# Top.net
KiCad netlist of a schematic drawn in Altium Designer
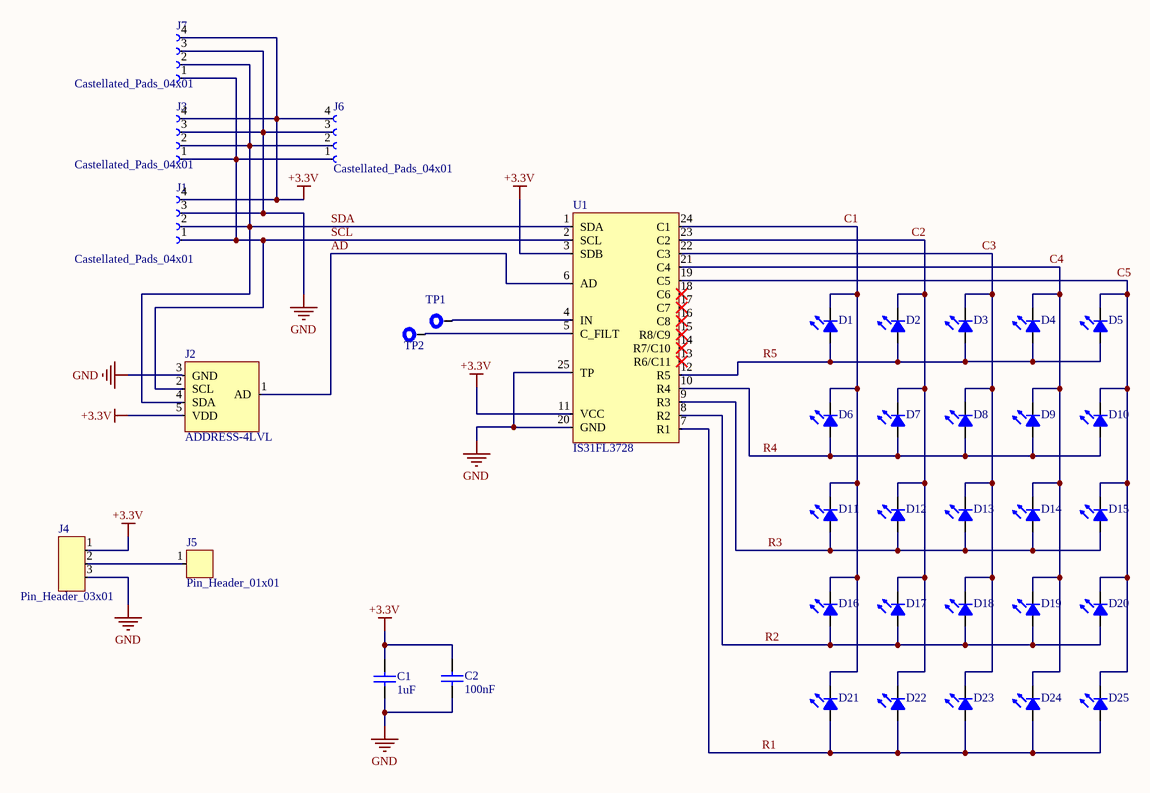
[diagram p0: Top.SchDoc]

(export (version "E")
  (design (tool "Eeschema 10.0.6"))
  (components
    (comp (ref "C1")
      (value "1uF")
      (footprint "CAP_0603")
      (fields (field (name "Comment") "CAP"))
      (libsource (lib "Passive") (part "CAP"))
    )
    (comp (ref "C2")
      (value "100nF")
      (footprint "CAP_0603")
      (fields (field (name "Comment") "CAP"))
      (libsource (lib "Passive") (part "CAP"))
    )
    (comp (ref "D1")
      (value "LED")
      (footprint "LED_0805")
      (fields (field (name "MANUFACTURER") "ROHM Semiconductor"))
      (libsource (lib "Rohm_Semi") (part "LED"))
    )
    (comp (ref "D2")
      (value "LED")
      (footprint "LED_0805")
      (fields (field (name "MANUFACTURER") "ROHM Semiconductor"))
      (libsource (lib "Rohm_Semi") (part "LED"))
    )
    (comp (ref "D3")
      (value "LED")
      (footprint "LED_0805")
      (fields (field (name "MANUFACTURER") "ROHM Semiconductor"))
      (libsource (lib "Rohm_Semi") (part "LED"))
    )
    (comp (ref "D4")
      (value "LED")
      (footprint "LED_0805")
      (fields (field (name "MANUFACTURER") "ROHM Semiconductor"))
      (libsource (lib "Rohm_Semi") (part "LED"))
    )
    (comp (ref "D5")
      (value "LED")
      (footprint "LED_0805")
      (fields (field (name "MANUFACTURER") "ROHM Semiconductor"))
      (libsource (lib "Rohm_Semi") (part "LED"))
    )
    (comp (ref "D6")
      (value "LED")
      (footprint "LED_0805")
      (fields (field (name "MANUFACTURER") "ROHM Semiconductor"))
      (libsource (lib "Rohm_Semi") (part "LED"))
    )
    (comp (ref "D7")
      (value "LED")
      (footprint "LED_0805")
      (fields (field (name "MANUFACTURER") "ROHM Semiconductor"))
      (libsource (lib "Rohm_Semi") (part "LED"))
    )
    (comp (ref "D8")
      (value "LED")
      (footprint "LED_0805")
      (fields (field (name "MANUFACTURER") "ROHM Semiconductor"))
      (libsource (lib "Rohm_Semi") (part "LED"))
    )
    (comp (ref "D9")
      (value "LED")
      (footprint "LED_0805")
      (fields (field (name "MANUFACTURER") "ROHM Semiconductor"))
      (libsource (lib "Rohm_Semi") (part "LED"))
    )
    (comp (ref "D10")
      (value "LED")
      (footprint "LED_0805")
      (fields (field (name "MANUFACTURER") "ROHM Semiconductor"))
      (libsource (lib "Rohm_Semi") (part "LED"))
    )
    (comp (ref "D11")
      (value "LED")
      (footprint "LED_0805")
      (fields (field (name "MANUFACTURER") "ROHM Semiconductor"))
      (libsource (lib "Rohm_Semi") (part "LED"))
    )
    (comp (ref "D12")
      (value "LED")
      (footprint "LED_0805")
      (fields (field (name "MANUFACTURER") "ROHM Semiconductor"))
      (libsource (lib "Rohm_Semi") (part "LED"))
    )
    (comp (ref "D13")
      (value "LED")
      (footprint "LED_0805")
      (fields (field (name "MANUFACTURER") "ROHM Semiconductor"))
      (libsource (lib "Rohm_Semi") (part "LED"))
    )
    (comp (ref "D14")
      (value "LED")
      (footprint "LED_0805")
      (fields (field (name "MANUFACTURER") "ROHM Semiconductor"))
      (libsource (lib "Rohm_Semi") (part "LED"))
    )
    (comp (ref "D15")
      (value "LED")
      (footprint "LED_0805")
      (fields (field (name "MANUFACTURER") "ROHM Semiconductor"))
      (libsource (lib "Rohm_Semi") (part "LED"))
    )
    (comp (ref "D16")
      (value "LED")
      (footprint "LED_0805")
      (fields (field (name "MANUFACTURER") "ROHM Semiconductor"))
      (libsource (lib "Rohm_Semi") (part "LED"))
    )
    (comp (ref "D17")
      (value "LED")
      (footprint "LED_0805")
      (fields (field (name "MANUFACTURER") "ROHM Semiconductor"))
      (libsource (lib "Rohm_Semi") (part "LED"))
    )
    (comp (ref "D18")
      (value "LED")
      (footprint "LED_0805")
      (fields (field (name "MANUFACTURER") "ROHM Semiconductor"))
      (libsource (lib "Rohm_Semi") (part "LED"))
    )
    (comp (ref "D19")
      (value "LED")
      (footprint "LED_0805")
      (fields (field (name "MANUFACTURER") "ROHM Semiconductor"))
      (libsource (lib "Rohm_Semi") (part "LED"))
    )
    (comp (ref "D20")
      (value "LED")
      (footprint "LED_0805")
      (fields (field (name "MANUFACTURER") "ROHM Semiconductor"))
      (libsource (lib "Rohm_Semi") (part "LED"))
    )
    (comp (ref "D21")
      (value "LED")
      (footprint "LED_0805")
      (fields (field (name "MANUFACTURER") "ROHM Semiconductor"))
      (libsource (lib "Rohm_Semi") (part "LED"))
    )
    (comp (ref "D22")
      (value "LED")
      (footprint "LED_0805")
      (fields (field (name "MANUFACTURER") "ROHM Semiconductor"))
      (libsource (lib "Rohm_Semi") (part "LED"))
    )
    (comp (ref "D23")
      (value "LED")
      (footprint "LED_0805")
      (fields (field (name "MANUFACTURER") "ROHM Semiconductor"))
      (libsource (lib "Rohm_Semi") (part "LED"))
    )
    (comp (ref "D24")
      (value "LED")
      (footprint "LED_0805")
      (fields (field (name "MANUFACTURER") "ROHM Semiconductor"))
      (libsource (lib "Rohm_Semi") (part "LED"))
    )
    (comp (ref "D25")
      (value "LED")
      (footprint "LED_0805")
      (fields (field (name "MANUFACTURER") "ROHM Semiconductor"))
      (libsource (lib "Rohm_Semi") (part "LED"))
    )
    (comp (ref "J1")
      (value "Castellated_Pads_04x01")
      (footprint "04X01_Castellated_Pad_1MM")
      (libsource (lib "Connectors") (part "Castellated_Pads_04x01"))
    )
    (comp (ref "J2")
      (value "ADDRESS-4LVL")
      (footprint "ADDRESS-4LVL")
      (libsource (lib "SolderJumper") (part "ADDRESS-4LVL"))
    )
    (comp (ref "J3")
      (value "Castellated_Pads_04x01")
      (footprint "04X01_Castellated_Pad_1MM")
      (libsource (lib "Connectors") (part "Castellated_Pads_04x01"))
    )
    (comp (ref "J4")
      (value "Pin_Header_03x01")
      (footprint "03x01_Header_5mm_MAL_DOWN")
      (libsource (lib "Connectors") (part "Pin_Header_03x01"))
    )
    (comp (ref "J5")
      (value "Pin_Header_01x01")
      (footprint "01x01_Header_2.54mm_MAL")
      (libsource (lib "Connectors") (part "Pin_Header_01x01"))
    )
    (comp (ref "J6")
      (value "Castellated_Pads_04x01")
      (footprint "04X01_Castellated_Pad_1MM")
      (libsource (lib "") (part "Castellated_Pads_04x01_1"))
    )
    (comp (ref "J7")
      (value "Castellated_Pads_04x01")
      (footprint "04X01_Castellated_Pad_1MM")
      (libsource (lib "Connectors") (part "Castellated_Pads_04x01"))
    )
    (comp (ref "TP1")
      (value "Testpoint 2mm")
      (footprint "TESTPOINT")
      (libsource (lib "Testpoint") (part "Testpoint 2mm"))
    )
    (comp (ref "TP2")
      (value "Testpoint 2mm")
      (footprint "TESTPOINT")
      (libsource (lib "Testpoint") (part "Testpoint 2mm"))
    )
    (comp (ref "U1")
      (value "IS31FL3728")
      (footprint "QFN50P395X400X80_HS-25N")
      (description "8x8 IIC Led Driver")
      (fields (field (name "MANUFACTURER") "ISSI"))
      (libsource (lib "ISSI") (part "IS31FL3728"))
    )
  )
  (nets
    (net (code "1") (name "+3.3V") (class "Default")
      (node (ref "C1") (pin "2") (pinfunction "2_2") (pintype "passive"))
      (node (ref "C2") (pin "2") (pinfunction "2_2") (pintype "passive"))
      (node (ref "J1") (pin "4") (pintype "passive"))
      (node (ref "J2") (pin "5") (pinfunction "VDD_5") (pintype "passive"))
      (node (ref "J3") (pin "4") (pintype "passive"))
      (node (ref "J4") (pin "1") (pintype "passive"))
      (node (ref "J6") (pin "4") (pintype "passive"))
      (node (ref "J7") (pin "4") (pintype "passive"))
      (node (ref "U1") (pin "11") (pinfunction "VCC_11") (pintype "power_in"))
      (node (ref "U1") (pin "3") (pinfunction "SDB_3") (pintype "input"))
    )
    (net (code "2") (name "/AD") (class "Default")
      (node (ref "J2") (pin "1") (pinfunction "AD_1") (pintype "passive"))
      (node (ref "U1") (pin "6") (pinfunction "AD_6") (pintype "input"))
    )
    (net (code "3") (name "/C1") (class "Default")
      (node (ref "D1") (pin "1") (pinfunction "K_1") (pintype "passive"))
      (node (ref "D11") (pin "1") (pinfunction "K_1") (pintype "passive"))
      (node (ref "D16") (pin "1") (pinfunction "K_1") (pintype "passive"))
      (node (ref "D21") (pin "1") (pinfunction "K_1") (pintype "passive"))
      (node (ref "D6") (pin "1") (pinfunction "K_1") (pintype "passive"))
      (node (ref "U1") (pin "24") (pinfunction "C1_24") (pintype "bidirectional"))
    )
    (net (code "4") (name "/C2") (class "Default")
      (node (ref "D12") (pin "1") (pinfunction "K_1") (pintype "passive"))
      (node (ref "D17") (pin "1") (pinfunction "K_1") (pintype "passive"))
      (node (ref "D2") (pin "1") (pinfunction "K_1") (pintype "passive"))
      (node (ref "D22") (pin "1") (pinfunction "K_1") (pintype "passive"))
      (node (ref "D7") (pin "1") (pinfunction "K_1") (pintype "passive"))
      (node (ref "U1") (pin "23") (pinfunction "C2_23") (pintype "bidirectional"))
    )
    (net (code "5") (name "/C3") (class "Default")
      (node (ref "D13") (pin "1") (pinfunction "K_1") (pintype "passive"))
      (node (ref "D18") (pin "1") (pinfunction "K_1") (pintype "passive"))
      (node (ref "D23") (pin "1") (pinfunction "K_1") (pintype "passive"))
      (node (ref "D3") (pin "1") (pinfunction "K_1") (pintype "passive"))
      (node (ref "D8") (pin "1") (pinfunction "K_1") (pintype "passive"))
      (node (ref "U1") (pin "22") (pinfunction "C3_22") (pintype "bidirectional"))
    )
    (net (code "6") (name "/C4") (class "Default")
      (node (ref "D14") (pin "1") (pinfunction "K_1") (pintype "passive"))
      (node (ref "D19") (pin "1") (pinfunction "K_1") (pintype "passive"))
      (node (ref "D24") (pin "1") (pinfunction "K_1") (pintype "passive"))
      (node (ref "D4") (pin "1") (pinfunction "K_1") (pintype "passive"))
      (node (ref "D9") (pin "1") (pinfunction "K_1") (pintype "passive"))
      (node (ref "U1") (pin "21") (pinfunction "C4_21") (pintype "bidirectional"))
    )
    (net (code "7") (name "/C5") (class "Default")
      (node (ref "D10") (pin "1") (pinfunction "K_1") (pintype "passive"))
      (node (ref "D15") (pin "1") (pinfunction "K_1") (pintype "passive"))
      (node (ref "D20") (pin "1") (pinfunction "K_1") (pintype "passive"))
      (node (ref "D25") (pin "1") (pinfunction "K_1") (pintype "passive"))
      (node (ref "D5") (pin "1") (pinfunction "K_1") (pintype "passive"))
      (node (ref "U1") (pin "19") (pinfunction "C5_19") (pintype "bidirectional"))
    )
    (net (code "8") (name "/R1") (class "Default")
      (node (ref "D21") (pin "2") (pinfunction "A_2") (pintype "passive"))
      (node (ref "D22") (pin "2") (pinfunction "A_2") (pintype "passive"))
      (node (ref "D23") (pin "2") (pinfunction "A_2") (pintype "passive"))
      (node (ref "D24") (pin "2") (pinfunction "A_2") (pintype "passive"))
      (node (ref "D25") (pin "2") (pinfunction "A_2") (pintype "passive"))
      (node (ref "U1") (pin "7") (pinfunction "R1_7") (pintype "bidirectional"))
    )
    (net (code "9") (name "/R2") (class "Default")
      (node (ref "D16") (pin "2") (pinfunction "A_2") (pintype "passive"))
      (node (ref "D17") (pin "2") (pinfunction "A_2") (pintype "passive"))
      (node (ref "D18") (pin "2") (pinfunction "A_2") (pintype "passive"))
      (node (ref "D19") (pin "2") (pinfunction "A_2") (pintype "passive"))
      (node (ref "D20") (pin "2") (pinfunction "A_2") (pintype "passive"))
      (node (ref "U1") (pin "8") (pinfunction "R2_8") (pintype "bidirectional"))
    )
    (net (code "10") (name "/R3") (class "Default")
      (node (ref "D11") (pin "2") (pinfunction "A_2") (pintype "passive"))
      (node (ref "D12") (pin "2") (pinfunction "A_2") (pintype "passive"))
      (node (ref "D13") (pin "2") (pinfunction "A_2") (pintype "passive"))
      (node (ref "D14") (pin "2") (pinfunction "A_2") (pintype "passive"))
      (node (ref "D15") (pin "2") (pinfunction "A_2") (pintype "passive"))
      (node (ref "U1") (pin "9") (pinfunction "R3_9") (pintype "bidirectional"))
    )
    (net (code "11") (name "/R4") (class "Default")
      (node (ref "D10") (pin "2") (pinfunction "A_2") (pintype "passive"))
      (node (ref "D6") (pin "2") (pinfunction "A_2") (pintype "passive"))
      (node (ref "D7") (pin "2") (pinfunction "A_2") (pintype "passive"))
      (node (ref "D8") (pin "2") (pinfunction "A_2") (pintype "passive"))
      (node (ref "D9") (pin "2") (pinfunction "A_2") (pintype "passive"))
      (node (ref "U1") (pin "10") (pinfunction "R4_10") (pintype "bidirectional"))
    )
    (net (code "13") (name "/SCL") (class "Default")
      (node (ref "J1") (pin "1") (pintype "passive"))
      (node (ref "J2") (pin "2") (pinfunction "SCL_2") (pintype "passive"))
      (node (ref "J3") (pin "1") (pintype "passive"))
      (node (ref "J6") (pin "1") (pintype "passive"))
      (node (ref "J7") (pin "1") (pintype "passive"))
      (node (ref "U1") (pin "2") (pinfunction "SCL_2") (pintype "input"))
    )
    (net (code "14") (name "/SDA") (class "Default")
      (node (ref "J1") (pin "2") (pintype "passive"))
      (node (ref "J2") (pin "4") (pinfunction "SDA_4") (pintype "passive"))
      (node (ref "J3") (pin "2") (pintype "passive"))
      (node (ref "J6") (pin "2") (pintype "passive"))
      (node (ref "J7") (pin "2") (pintype "passive"))
      (node (ref "U1") (pin "1") (pinfunction "SDA_1") (pintype "bidirectional"))
    )
    (net (code "15") (name "GND") (class "Default")
      (node (ref "C1") (pin "1") (pinfunction "1_1") (pintype "passive"))
      (node (ref "C2") (pin "1") (pinfunction "1_1") (pintype "passive"))
      (node (ref "J1") (pin "3") (pintype "passive"))
      (node (ref "J2") (pin "3") (pinfunction "GND_3") (pintype "passive"))
      (node (ref "J3") (pin "3") (pintype "passive"))
      (node (ref "J4") (pin "3") (pintype "passive"))
      (node (ref "J6") (pin "3") (pintype "passive"))
      (node (ref "J7") (pin "3") (pintype "passive"))
      (node (ref "U1") (pin "20") (pinfunction "GND_20") (pintype "power_in"))
      (node (ref "U1") (pin "25") (pinfunction "TP_25") (pintype "power_in"))
    )
    (net (code "16") (name "Net-(D1-A)") (class "Default")
      (node (ref "D1") (pin "2") (pinfunction "A_2") (pintype "passive"))
      (node (ref "D2") (pin "2") (pinfunction "A_2") (pintype "passive"))
      (node (ref "D3") (pin "2") (pinfunction "A_2") (pintype "passive"))
      (node (ref "D4") (pin "2") (pinfunction "A_2") (pintype "passive"))
      (node (ref "D5") (pin "2") (pinfunction "A_2") (pintype "passive"))
      (node (ref "U1") (pin "12") (pinfunction "R5_12") (pintype "bidirectional"))
    )
    (net (code "17") (name "Net-(J4-Pad2)") (class "Default")
      (node (ref "J4") (pin "2") (pintype "passive"))
      (node (ref "J5") (pin "1") (pintype "passive"))
    )
    (net (code "18") (name "Net-(U1-C_FILT)") (class "Default")
      (node (ref "TP2") (pin "1") (pinfunction "1_1") (pintype "power_in"))
      (node (ref "U1") (pin "5") (pinfunction "C_FILT_5") (pintype "passive"))
    )
    (net (code "19") (name "Net-(U1-IN)") (class "Default")
      (node (ref "TP1") (pin "1") (pinfunction "1_1") (pintype "power_in"))
      (node (ref "U1") (pin "4") (pinfunction "IN_4") (pintype "input"))
    )
    (net (code "20") (name "unconnected-(U1-C6-Pad18)") (class "Default")
      (node (ref "U1") (pin "18") (pinfunction "C6_18") (pintype "bidirectional+no_connect"))
    )
    (net (code "21") (name "unconnected-(U1-C7-Pad17)") (class "Default")
      (node (ref "U1") (pin "17") (pinfunction "C7_17") (pintype "bidirectional+no_connect"))
    )
    (net (code "22") (name "unconnected-(U1-C8-Pad16)") (class "Default")
      (node (ref "U1") (pin "16") (pinfunction "C8_16") (pintype "bidirectional+no_connect"))
    )
    (net (code "23") (name "unconnected-(U1-R6{slash}C11-Pad13)") (class "Default")
      (node (ref "U1") (pin "13") (pinfunction "R6/C11_13") (pintype "bidirectional+no_connect"))
    )
    (net (code "24") (name "unconnected-(U1-R7{slash}C10-Pad14)") (class "Default")
      (node (ref "U1") (pin "14") (pinfunction "R7/C10_14") (pintype "bidirectional+no_connect"))
    )
    (net (code "25") (name "unconnected-(U1-R8{slash}C9-Pad15)") (class "Default")
      (node (ref "U1") (pin "15") (pinfunction "R8/C9_15") (pintype "bidirectional+no_connect"))
    )
  )
)
